# SCH.net
KiCad netlist of a schematic drawn in EasyEDA Pro
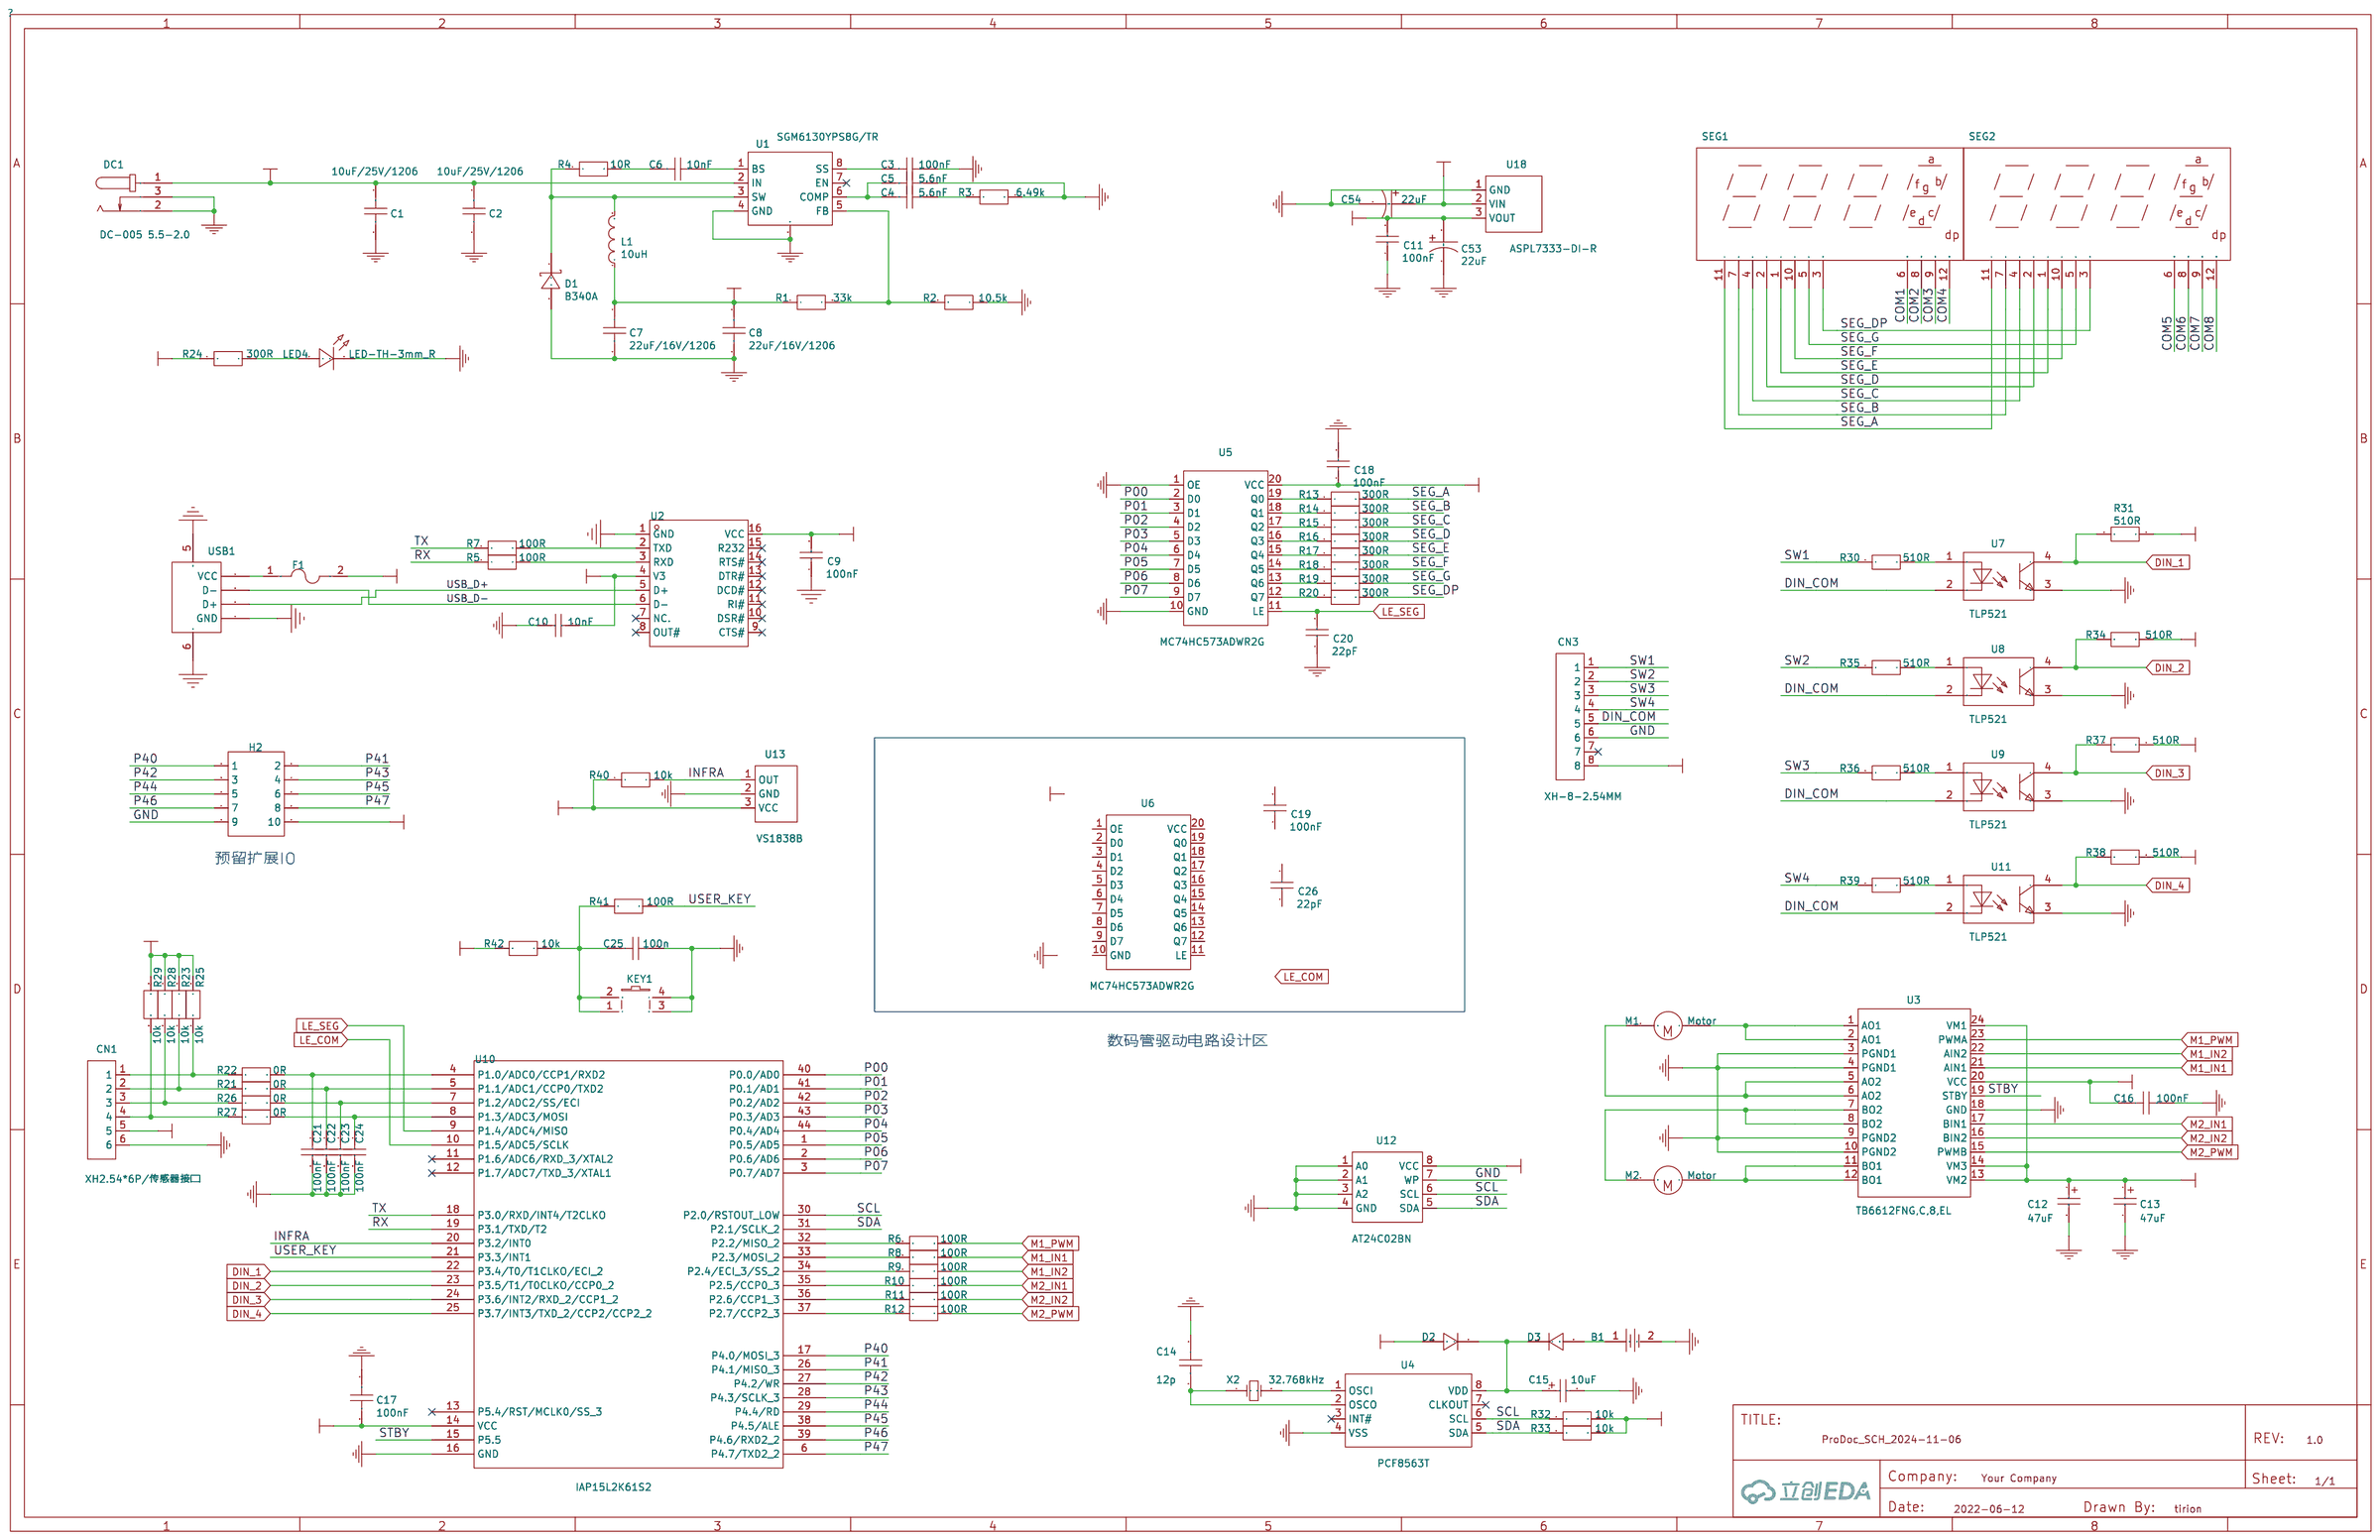
[diagram p0: schematic sheet]

(export (version "E")
  (design (tool "Eeschema 10.0.6"))
  (components
    (comp (ref "B1")
      (value "CR1220-2")
      (footprint "easyedapro:BAT-SMD_CR1220-2")
      (fields (field (name "Manufacturer") "Q&J"))
      (libsource (lib "easyedapro") (part "CR1220-2"))
    )
    (comp (ref "C1")
      (value "10uF/25V/1206")
      (footprint "easyedapro:C1206")
      (libsource (lib "easyedapro") (part "10uF/25V/1206"))
    )
    (comp (ref "C2")
      (value "10uF/25V/1206")
      (footprint "easyedapro:C1206")
      (libsource (lib "easyedapro") (part "10uF/25V/1206"))
    )
    (comp (ref "C3") (value "100nF") (footprint "easyedapro:C0805") (libsource (lib "") (part "100nF_1")))
    (comp (ref "C4")
      (value "5.6nF")
      (footprint "easyedapro:C0805")
      (libsource (lib "easyedapro") (part "5.6nF"))
    )
    (comp (ref "C5")
      (value "5.6nF")
      (footprint "easyedapro:C0805")
      (libsource (lib "easyedapro") (part "5.6nF"))
    )
    (comp (ref "C6")
      (value "10nF")
      (footprint "easyedapro:C0805")
      (libsource (lib "easyedapro") (part "10nF"))
    )
    (comp (ref "C7")
      (value "22uF/16V/1206")
      (footprint "easyedapro:C1206")
      (libsource (lib "easyedapro") (part "22uF/16V/1206"))
    )
    (comp (ref "C8")
      (value "22uF/16V/1206")
      (footprint "easyedapro:C1206")
      (libsource (lib "easyedapro") (part "22uF/16V/1206"))
    )
    (comp (ref "C9")
      (value "100nF")
      (footprint "easyedapro:C_C0805")
      (fields (field (name "Manufacturer Part") "0805F104M500NT") (field (name "Manufacturer") "FH"))
      (libsource (lib "easyedapro") (part "100nF"))
    )
    (comp (ref "C10")
      (value "10nF")
      (footprint "easyedapro:C_C0805")
      (fields (field (name "Manufacturer Part") "0805F104M500NT") (field (name "Manufacturer") "FH"))
      (libsource (lib "easyedapro") (part "100nF"))
    )
    (comp (ref "C11")
      (value "100nF")
      (footprint "easyedapro:C_C0805")
      (fields (field (name "Manufacturer Part") "0805F104M500NT") (field (name "Manufacturer") "FH"))
      (libsource (lib "easyedapro") (part "100nF"))
    )
    (comp (ref "C12")
      (value "47uF")
      (footprint "easyedapro:C_Ele_SMD_3x5.4mm")
      (libsource (lib "easyedapro") (part "CAP"))
    )
    (comp (ref "C13")
      (value "47uF")
      (footprint "easyedapro:C_Ele_SMD_3x5.4mm")
      (libsource (lib "easyedapro") (part "CAP"))
    )
    (comp (ref "C14")
      (value "12p")
      (footprint "easyedapro:C0805")
      (libsource (lib "easyedapro") (part "12p"))
    )
    (comp (ref "C15")
      (value "10uF")
      (footprint "easyedapro:C_Ele_SMD_3x5.4mm")
      (libsource (lib "easyedapro") (part "CAP"))
    )
    (comp (ref "C16") (value "100nF") (footprint "easyedapro:C0805") (libsource (lib "") (part "100nF_1")))
    (comp (ref "C17") (value "100nF") (footprint "easyedapro:C0805") (libsource (lib "") (part "100nF_1")))
    (comp (ref "C18")
      (value "100nF")
      (footprint "easyedapro:C_C0805")
      (fields (field (name "Manufacturer Part") "0805F104M500NT") (field (name "Manufacturer") "FH"))
      (libsource (lib "easyedapro") (part "100nF"))
    )
    (comp (ref "C19")
      (value "100nF")
      (footprint "easyedapro:C_C0805")
      (fields (field (name "Manufacturer Part") "0805F104M500NT") (field (name "Manufacturer") "FH"))
      (libsource (lib "easyedapro") (part "100nF"))
    )
    (comp (ref "C20")
      (value "22pF")
      (footprint "easyedapro:C_C0805")
      (fields (field (name "Manufacturer Part") "0805F104M500NT") (field (name "Manufacturer") "FH"))
      (libsource (lib "easyedapro") (part "100nF"))
    )
    (comp (ref "C21")
      (value "100nF")
      (footprint "easyedapro:C_C0805")
      (fields (field (name "Manufacturer Part") "0805F104M500NT") (field (name "Manufacturer") "FH"))
      (libsource (lib "easyedapro") (part "100nF"))
    )
    (comp (ref "C22")
      (value "100nF")
      (footprint "easyedapro:C_C0805")
      (fields (field (name "Manufacturer Part") "0805F104M500NT") (field (name "Manufacturer") "FH"))
      (libsource (lib "easyedapro") (part "100nF"))
    )
    (comp (ref "C23")
      (value "100nF")
      (footprint "easyedapro:C_C0805")
      (fields (field (name "Manufacturer Part") "0805F104M500NT") (field (name "Manufacturer") "FH"))
      (libsource (lib "easyedapro") (part "100nF"))
    )
    (comp (ref "C24")
      (value "100nF")
      (footprint "easyedapro:C_C0805")
      (fields (field (name "Manufacturer Part") "0805F104M500NT") (field (name "Manufacturer") "FH"))
      (libsource (lib "easyedapro") (part "100nF"))
    )
    (comp (ref "C25")
      (value "100n")
      (footprint "easyedapro:C0805")
      (libsource (lib "easyedapro") (part "100n"))
    )
    (comp (ref "C26")
      (value "22pF")
      (footprint "easyedapro:C_C0805")
      (fields (field (name "Manufacturer Part") "0805F104M500NT") (field (name "Manufacturer") "FH"))
      (libsource (lib "easyedapro") (part "100nF"))
    )
    (comp (ref "C53")
      (value "22uF")
      (footprint "easyedapro:CAP-SMD_BD6.3-L6.6-W6.6-FD")
      (fields (field (name "Manufacturer") "Honor Elec"))
      (libsource (lib "easyedapro") (part "22uF"))
    )
    (comp (ref "C54")
      (value "22uF")
      (footprint "easyedapro:CAP-SMD_BD6.3-L6.6-W6.6-FD")
      (fields (field (name "Manufacturer") "Honor Elec"))
      (libsource (lib "easyedapro") (part "22uF"))
    )
    (comp (ref "CN1")
      (value "XH2.54*6P/传感器接口")
      (footprint "easyedapro:CONN-TH_XH2.54-6P")
      (fields (field (name "Manufacturer Part") "XH2.54*6P_直插"))
      (libsource (lib "easyedapro") (part "XH2.54*6P/传感器接口"))
    )
    (comp (ref "CN3")
      (value "XH-8-2.54MM")
      (footprint "easyedapro:CONN-TH_8P-P2.50-XH2.54-8P")
      (libsource (lib "easyedapro") (part "XH-8-2.54MM"))
    )
    (comp (ref "D1")
      (value "B340A")
      (footprint "easyedapro:SMA_L4.3-W2.6-LS5.2-RD")
      (fields (field (name "Manufacturer") "MDD"))
      (libsource (lib "easyedapro") (part "B340A"))
    )
    (comp (ref "D2")
      (value "1N4148")
      (footprint "easyedapro:DO-35_BD2.0-L4.2-P8.20-D0.5-RD")
      (fields (field (name "Manufacturer") "STMicroelectronics"))
      (libsource (lib "easyedapro") (part "1N4148"))
    )
    (comp (ref "D3")
      (value "1N4148")
      (footprint "easyedapro:DO-35_BD2.0-L4.2-P8.20-D0.5-RD")
      (fields (field (name "Manufacturer") "STMicroelectronics"))
      (libsource (lib "easyedapro") (part "1N4148"))
    )
    (comp (ref "DC1")
      (value "DC-005 5.5-2.0")
      (footprint "easyedapro:DC-IN-TH_DC005")
      (fields (field (name "Manufacturer") "Shenzhen Cankemeng"))
      (libsource (lib "easyedapro") (part "DC-005 5.5-2.0"))
    )
    (comp (ref "F1")
      (value "ASMD1210-075")
      (footprint "easyedapro:F1210")
      (description "最大电压:6V;最大电流:100A;保持电流:750mA;跳闸电流:1.5A;")
      (fields (field (name "Manufacturer") "JDTfuse(集电通)"))
      (libsource (lib "easyedapro") (part "ASMD1210-075"))
    )
    (comp (ref "H2")
      (value "HDR-F-2.54_2x5")
      (footprint "easyedapro:HDR-F-2.54_2X5")
      (libsource (lib "easyedapro") (part "HDR-F-2.54_2x5"))
    )
    (comp (ref "KEY1")
      (value "K4-6×6_SMD")
      (footprint "easyedapro:KEY-SMD_4P-L6.0-W6.0-P3.90-LS10.0")
      (fields (field (name "Manufacturer Part") "K2-6639SP-D4SC-04") (field (name "Manufacturer") "韩国韩荣"))
      (libsource (lib "easyedapro") (part "K4-6×6_SMD"))
    )
    (comp (ref "L1")
      (value "10uH")
      (footprint "easyedapro:IND-SMD_L8.3-W8.3")
      (fields
        (field (name "Manufacturer Part") "1217AS-H-100M=P3")
        (field (name "Manufacturer") "Murata Electronics")
      )
      (libsource (lib "easyedapro") (part "10uH"))
    )
    (comp (ref "LED4")
      (value "LED-TH-3mm_R")
      (footprint "easyedapro:LED-TH_BD3.0_RED")
      (fields
        (field (name "Manufacturer Part") "204-10SDRD/S530-A3-L")
        (field (name "Manufacturer") "EVERLIGHT(台湾亿光)")
      )
      (libsource (lib "easyedapro") (part "LED-TH-3mm_R"))
    )
    (comp (ref "M1")
      (value "Motor")
      (footprint "easyedapro:CONN-TH_2P-P5.08-WJ500V-5.08-2P")
      (libsource (lib "easyedapro") (part "Motor"))
    )
    (comp (ref "M2")
      (value "Motor")
      (footprint "easyedapro:CONN-TH_2P-P5.08-WJ500V-5.08-2P")
      (libsource (lib "easyedapro") (part "Motor"))
    )
    (comp (ref "R1") (value "33k") (footprint "easyedapro:R0805") (libsource (lib "easyedapro") (part "33k")))
    (comp (ref "R2")
      (value "10.5k")
      (footprint "easyedapro:R0805")
      (libsource (lib "easyedapro") (part "10.5k"))
    )
    (comp (ref "R3")
      (value "6.49k")
      (footprint "easyedapro:R0805")
      (libsource (lib "easyedapro") (part "6.49k"))
    )
    (comp (ref "R4") (value "10R") (footprint "easyedapro:R0805") (libsource (lib "easyedapro") (part "10R")))
    (comp (ref "R5")
      (value "100R")
      (footprint "easyedapro:R0805")
      (libsource (lib "easyedapro") (part "100R"))
    )
    (comp (ref "R6")
      (value "100R")
      (footprint "easyedapro:R0805")
      (libsource (lib "easyedapro") (part "100R"))
    )
    (comp (ref "R7")
      (value "100R")
      (footprint "easyedapro:R0805")
      (libsource (lib "easyedapro") (part "100R"))
    )
    (comp (ref "R8")
      (value "100R")
      (footprint "easyedapro:R0805")
      (libsource (lib "easyedapro") (part "100R"))
    )
    (comp (ref "R9")
      (value "100R")
      (footprint "easyedapro:R0805")
      (libsource (lib "easyedapro") (part "100R"))
    )
    (comp (ref "R10")
      (value "100R")
      (footprint "easyedapro:R0805")
      (libsource (lib "easyedapro") (part "100R"))
    )
    (comp (ref "R11")
      (value "100R")
      (footprint "easyedapro:R0805")
      (libsource (lib "easyedapro") (part "100R"))
    )
    (comp (ref "R12")
      (value "100R")
      (footprint "easyedapro:R0805")
      (libsource (lib "easyedapro") (part "100R"))
    )
    (comp (ref "R13")
      (value "300R")
      (footprint "easyedapro:R0805")
      (libsource (lib "easyedapro") (part "300R"))
    )
    (comp (ref "R14")
      (value "300R")
      (footprint "easyedapro:R0805")
      (libsource (lib "easyedapro") (part "300R"))
    )
    (comp (ref "R15")
      (value "300R")
      (footprint "easyedapro:R0805")
      (libsource (lib "easyedapro") (part "300R"))
    )
    (comp (ref "R16")
      (value "300R")
      (footprint "easyedapro:R0805")
      (libsource (lib "easyedapro") (part "300R"))
    )
    (comp (ref "R17")
      (value "300R")
      (footprint "easyedapro:R0805")
      (libsource (lib "easyedapro") (part "300R"))
    )
    (comp (ref "R18")
      (value "300R")
      (footprint "easyedapro:R0805")
      (libsource (lib "easyedapro") (part "300R"))
    )
    (comp (ref "R19")
      (value "300R")
      (footprint "easyedapro:R0805")
      (libsource (lib "easyedapro") (part "300R"))
    )
    (comp (ref "R20")
      (value "300R")
      (footprint "easyedapro:R0805")
      (libsource (lib "easyedapro") (part "300R"))
    )
    (comp (ref "R21") (value "0R") (footprint "easyedapro:R0805") (libsource (lib "easyedapro") (part "0R")))
    (comp (ref "R22") (value "0R") (footprint "easyedapro:R0805") (libsource (lib "easyedapro") (part "0R")))
    (comp (ref "R23")
      (value "10k")
      (footprint "easyedapro:R0805")
      (libsource (lib "easyedapro") (part "10k"))
    )
    (comp (ref "R24")
      (value "300R")
      (footprint "easyedapro:R0805")
      (libsource (lib "easyedapro") (part "300R"))
    )
    (comp (ref "R25")
      (value "10k")
      (footprint "easyedapro:R0805")
      (libsource (lib "easyedapro") (part "10k"))
    )
    (comp (ref "R26") (value "0R") (footprint "easyedapro:R0805") (libsource (lib "easyedapro") (part "0R")))
    (comp (ref "R27") (value "0R") (footprint "easyedapro:R0805") (libsource (lib "easyedapro") (part "0R")))
    (comp (ref "R28")
      (value "10k")
      (footprint "easyedapro:R0805")
      (libsource (lib "easyedapro") (part "10k"))
    )
    (comp (ref "R29")
      (value "10k")
      (footprint "easyedapro:R0805")
      (libsource (lib "easyedapro") (part "10k"))
    )
    (comp (ref "R30")
      (value "510R")
      (footprint "easyedapro:R0805")
      (libsource (lib "easyedapro") (part "510R"))
    )
    (comp (ref "R31")
      (value "510R")
      (footprint "easyedapro:R0805")
      (libsource (lib "easyedapro") (part "510R"))
    )
    (comp (ref "R32")
      (value "10k")
      (footprint "easyedapro:R0805")
      (libsource (lib "easyedapro") (part "10k"))
    )
    (comp (ref "R33")
      (value "10k")
      (footprint "easyedapro:R0805")
      (libsource (lib "easyedapro") (part "10k"))
    )
    (comp (ref "R34")
      (value "510R")
      (footprint "easyedapro:R0805")
      (libsource (lib "easyedapro") (part "510R"))
    )
    (comp (ref "R35")
      (value "510R")
      (footprint "easyedapro:R0805")
      (libsource (lib "easyedapro") (part "510R"))
    )
    (comp (ref "R36")
      (value "510R")
      (footprint "easyedapro:R0805")
      (libsource (lib "easyedapro") (part "510R"))
    )
    (comp (ref "R37")
      (value "510R")
      (footprint "easyedapro:R0805")
      (libsource (lib "easyedapro") (part "510R"))
    )
    (comp (ref "R38")
      (value "510R")
      (footprint "easyedapro:R0805")
      (libsource (lib "easyedapro") (part "510R"))
    )
    (comp (ref "R39")
      (value "510R")
      (footprint "easyedapro:R0805")
      (libsource (lib "easyedapro") (part "510R"))
    )
    (comp (ref "R40")
      (value "10k")
      (footprint "easyedapro:R0805")
      (libsource (lib "easyedapro") (part "10k"))
    )
    (comp (ref "R41")
      (value "100R")
      (footprint "easyedapro:R0805")
      (libsource (lib "easyedapro") (part "100R"))
    )
    (comp (ref "R42")
      (value "10k")
      (footprint "easyedapro:R0805")
      (libsource (lib "easyedapro") (part "10k"))
    )
    (comp (ref "SEG1")
      (value "0.36寸4位数码管")
      (footprint "easyedapro:LED-SEG-TH_FJ5461AH")
      (fields (field (name "Manufacturer Part") "FJ5461BH 纯红") (field (name "Manufacturer") "ReliaPro"))
      (libsource (lib "easyedapro") (part "0.36寸4位数码管"))
    )
    (comp (ref "SEG2")
      (value "0.36寸4位数码管")
      (footprint "easyedapro:LED-SEG-TH_FJ5461AH")
      (fields (field (name "Manufacturer Part") "FJ5461BH 纯红") (field (name "Manufacturer") "ReliaPro"))
      (libsource (lib "easyedapro") (part "0.36寸4位数码管"))
    )
    (comp (ref "U1")
      (value "SGM6130YPS8G/TR")
      (footprint "easyedapro:SOIC-8_L5.0-W4.0-P1.27-LS6.0-BL-EP2.0")
      (fields (field (name "Manufacturer") "SGMICRO"))
      (libsource (lib "easyedapro") (part "SGM6130YPS8G/TR"))
    )
    (comp (ref "U2")
      (value "CH340C")
      (footprint "easyedapro:SOP-16_L10.0-W3.9-P1.27-LS6.0-BL")
      (description "应用功能:收发器;接口协议:USB 2.0;数据速率:2Mbps;")
      (fields (field (name "Manufacturer") "WCH(南京沁恒)"))
      (libsource (lib "easyedapro") (part "CH340C"))
    )
    (comp (ref "U3")
      (value "TB6612FNG,C,8,EL")
      (footprint "easyedapro:SSOP-24_L8.3-W5.6-P0.65-LS7.6-BL")
      (fields (field (name "Manufacturer") "TOSHIBA"))
      (libsource (lib "easyedapro") (part "TB6612FNG,C,8,EL"))
    )
    (comp (ref "U4")
      (value "PCF8563T")
      (footprint "easyedapro:SOIC-8_L5.0-W4.0-P1.27-LS6.0-BL")
      (fields (field (name "Manufacturer Part") "PCF8563T/5,518") (field (name "Manufacturer") "NXP"))
      (libsource (lib "easyedapro") (part "PCF8563T"))
    )
    (comp (ref "U5")
      (value "MC74HC573ADWR2G")
      (footprint "easyedapro:SOIC-20_L13.0-W7.6-P1.27-LS10.3-BL")
      (fields (field (name "Manufacturer") "ON Semicon"))
      (libsource (lib "easyedapro") (part "MC74HC573ADWR2G"))
    )
    (comp (ref "U6")
      (value "MC74HC573ADWR2G")
      (footprint "easyedapro:SOIC-20_L13.0-W7.6-P1.27-LS10.3-BL")
      (fields (field (name "Manufacturer") "ON Semicon"))
      (libsource (lib "easyedapro") (part "MC74HC573ADWR2G"))
    )
    (comp (ref "U7")
      (value "TLP521")
      (footprint "easyedapro:SOP-4_L6.4-W4.6-P2.54-LS10.2-TL")
      (libsource (lib "easyedapro") (part "TLP521"))
    )
    (comp (ref "U8")
      (value "TLP521")
      (footprint "easyedapro:SOP-4_L6.4-W4.6-P2.54-LS10.2-TL")
      (libsource (lib "easyedapro") (part "TLP521"))
    )
    (comp (ref "U9")
      (value "TLP521")
      (footprint "easyedapro:SOP-4_L6.4-W4.6-P2.54-LS10.2-TL")
      (libsource (lib "easyedapro") (part "TLP521"))
    )
    (comp (ref "U10")
      (value "IAP15L2K61S2")
      (footprint "easyedapro:QFP-LQFP-44")
      (libsource (lib "easyedapro") (part "IAP15L2K61S2"))
    )
    (comp (ref "U11")
      (value "TLP521")
      (footprint "easyedapro:SOP-4_L6.4-W4.6-P2.54-LS10.2-TL")
      (libsource (lib "easyedapro") (part "TLP521"))
    )
    (comp (ref "U12")
      (value "AT24C02BN")
      (footprint "easyedapro:SOP-8_L4.9-W3.9-P1.27-LS6.0-TL")
      (libsource (lib "easyedapro") (part "AT24C02BN"))
    )
    (comp (ref "U13")
      (value "VS1838B")
      (footprint "easyedapro:OPTO-TH_VS1838B")
      (libsource (lib "easyedapro") (part "VS1838B"))
    )
    (comp (ref "U18")
      (value "ASPL7333-DI-R")
      (footprint "easyedapro:SOT-89-3_L4.5-W2.5-P1.50-LS4.2-BR")
      (fields (field (name "Manufacturer") "Ascend(安森德)"))
      (libsource (lib "easyedapro") (part "ASPL7333-DI-R"))
    )
    (comp (ref "USB1")
      (value "921-111A1010D10200")
      (footprint "easyedapro:USB-B_TH_USB-B-FEMALE-90")
      (description "连接器类型:Type-B;标准:USB 2.0;公母:母;端口数量:1;触点数量:4P;")
      (fields (field (name "Manufacturer") "精拓金"))
      (libsource (lib "easyedapro") (part "USB-B-Female-90"))
    )
    (comp (ref "X2")
      (value "32.768kHz")
      (footprint "easyedapro:OSC-TH_BD2.0-P0.70-D0.3")
      (description "晶振类型:直插晶振;频率:32.768kHz;常温频差:±10ppm;外接负载电容:12.5pF;频率稳定度(全温):-;")
      (fields (field (name "Manufacturer Part") "X206032768KGB2SC") (field (name "Manufacturer") "YXC(扬兴晶振)"))
      (libsource (lib "easyedapro") (part "X206032768KGB2SC"))
    )
  )
  (nets
    (net (code "1") (name "+3V3") (class "Default")
      (node (ref "C10") (pin "1") (pinfunction "1_1") (pintype "unspecified"))
      (node (ref "C11") (pin "2") (pinfunction "2_2") (pintype "unspecified"))
      (node (ref "C16") (pin "1") (pinfunction "1_1") (pintype "unspecified"))
      (node (ref "C17") (pin "2") (pinfunction "2_2") (pintype "unspecified"))
      (node (ref "C18") (pin "1") (pinfunction "1_1") (pintype "unspecified"))
      (node (ref "C53") (pin "1") (pinfunction "1_1") (pintype "unspecified"))
      (node (ref "C7") (pin "1") (pinfunction "1_1") (pintype "unspecified"))
      (node (ref "C8") (pin "1") (pinfunction "1_1") (pintype "unspecified"))
      (node (ref "C9") (pin "2") (pinfunction "2_2") (pintype "unspecified"))
      (node (ref "CN1") (pin "5") (pinfunction "5_5") (pintype "unspecified"))
      (node (ref "D2") (pin "2") (pinfunction "2_2") (pintype "unspecified"))
      (node (ref "H2") (pin "10") (pinfunction "10_10") (pintype "unspecified"))
      (node (ref "L1") (pin "1") (pinfunction "1_1") (pintype "unspecified"))
      (node (ref "R1") (pin "1") (pinfunction "1_1") (pintype "unspecified"))
      (node (ref "R23") (pin "1") (pinfunction "1_1") (pintype "unspecified"))
      (node (ref "R24") (pin "2") (pinfunction "2_2") (pintype "unspecified"))
      (node (ref "R25") (pin "1") (pinfunction "1_1") (pintype "unspecified"))
      (node (ref "R28") (pin "1") (pinfunction "1_1") (pintype "unspecified"))
      (node (ref "R29") (pin "1") (pinfunction "1_1") (pintype "unspecified"))
      (node (ref "R31") (pin "1") (pinfunction "1_1") (pintype "unspecified"))
      (node (ref "R32") (pin "2") (pinfunction "2_2") (pintype "unspecified"))
      (node (ref "R33") (pin "2") (pinfunction "2_2") (pintype "unspecified"))
      (node (ref "R34") (pin "1") (pinfunction "1_1") (pintype "unspecified"))
      (node (ref "R37") (pin "1") (pinfunction "1_1") (pintype "unspecified"))
      (node (ref "R38") (pin "1") (pinfunction "1_1") (pintype "unspecified"))
      (node (ref "R40") (pin "1") (pinfunction "1_1") (pintype "unspecified"))
      (node (ref "R42") (pin "2") (pinfunction "2_2") (pintype "unspecified"))
      (node (ref "U10") (pin "14") (pinfunction "VCC_14") (pintype "unspecified"))
      (node (ref "U12") (pin "8") (pinfunction "VCC_8") (pintype "unspecified"))
      (node (ref "U13") (pin "3") (pinfunction "VCC_3") (pintype "unspecified"))
      (node (ref "U18") (pin "3") (pinfunction "VOUT_3") (pintype "unspecified"))
      (node (ref "U2") (pin "16") (pinfunction "VCC_16") (pintype "unspecified"))
      (node (ref "U2") (pin "4") (pinfunction "V3_4") (pintype "unspecified"))
      (node (ref "U3") (pin "20") (pinfunction "VCC_20") (pintype "unspecified"))
      (node (ref "U5") (pin "20") (pinfunction "VCC_20") (pintype "unspecified"))
    )
    (net (code "2") (name "/COM1") (class "Default")
      (node (ref "SEG1") (pin "6") (pinfunction "DIG4_6") (pintype "input"))
    )
    (net (code "3") (name "/COM2") (class "Default")
      (node (ref "SEG1") (pin "8") (pinfunction "DIG3_8") (pintype "input"))
    )
    (net (code "4") (name "/COM3") (class "Default")
      (node (ref "SEG1") (pin "9") (pinfunction "DIG2_9") (pintype "input"))
    )
    (net (code "5") (name "/COM4") (class "Default")
      (node (ref "SEG1") (pin "12") (pinfunction "DIG1_12") (pintype "input"))
    )
    (net (code "6") (name "/COM5") (class "Default")
      (node (ref "SEG2") (pin "6") (pinfunction "DIG4_6") (pintype "input"))
    )
    (net (code "7") (name "/COM6") (class "Default")
      (node (ref "SEG2") (pin "8") (pinfunction "DIG3_8") (pintype "input"))
    )
    (net (code "8") (name "/COM7") (class "Default")
      (node (ref "SEG2") (pin "9") (pinfunction "DIG2_9") (pintype "input"))
    )
    (net (code "9") (name "/COM8") (class "Default")
      (node (ref "SEG2") (pin "12") (pinfunction "DIG1_12") (pintype "input"))
    )
    (net (code "10") (name "/DIN_COM") (class "Default")
      (node (ref "CN3") (pin "5") (pinfunction "5_5") (pintype "unspecified"))
      (node (ref "U11") (pin "2") (pinfunction "2_2") (pintype "unspecified"))
      (node (ref "U7") (pin "2") (pinfunction "2_2") (pintype "unspecified"))
      (node (ref "U8") (pin "2") (pinfunction "2_2") (pintype "unspecified"))
      (node (ref "U9") (pin "2") (pinfunction "2_2") (pintype "unspecified"))
    )
    (net (code "11") (name "/INFRA") (class "Default")
      (node (ref "R40") (pin "2") (pinfunction "2_2") (pintype "unspecified"))
      (node (ref "U10") (pin "20") (pinfunction "P3.2/INT0_20") (pintype "unspecified"))
      (node (ref "U13") (pin "1") (pinfunction "OUT_1") (pintype "unspecified"))
    )
    (net (code "12") (name "/P00") (class "Default")
      (node (ref "U10") (pin "40") (pinfunction "P0.0/AD0_40") (pintype "bidirectional"))
      (node (ref "U5") (pin "2") (pinfunction "D0_2") (pintype "unspecified"))
    )
    (net (code "13") (name "/P01") (class "Default")
      (node (ref "U10") (pin "41") (pinfunction "P0.1/AD1_41") (pintype "bidirectional"))
      (node (ref "U5") (pin "3") (pinfunction "D1_3") (pintype "unspecified"))
    )
    (net (code "14") (name "/P02") (class "Default")
      (node (ref "U10") (pin "42") (pinfunction "P0.2/AD2_42") (pintype "bidirectional"))
      (node (ref "U5") (pin "4") (pinfunction "D2_4") (pintype "unspecified"))
    )
    (net (code "15") (name "/P03") (class "Default")
      (node (ref "U10") (pin "43") (pinfunction "P0.3/AD3_43") (pintype "bidirectional"))
      (node (ref "U5") (pin "5") (pinfunction "D3_5") (pintype "unspecified"))
    )
    (net (code "16") (name "/P04") (class "Default")
      (node (ref "U10") (pin "44") (pinfunction "P0.4/AD4_44") (pintype "bidirectional"))
      (node (ref "U5") (pin "6") (pinfunction "D4_6") (pintype "unspecified"))
    )
    (net (code "17") (name "/P05") (class "Default")
      (node (ref "U10") (pin "1") (pinfunction "P0.5/AD5_1") (pintype "bidirectional"))
      (node (ref "U5") (pin "7") (pinfunction "D5_7") (pintype "unspecified"))
    )
    (net (code "18") (name "/P06") (class "Default")
      (node (ref "U10") (pin "2") (pinfunction "P0.6/AD6_2") (pintype "bidirectional"))
      (node (ref "U5") (pin "8") (pinfunction "D6_8") (pintype "unspecified"))
    )
    (net (code "19") (name "/P07") (class "Default")
      (node (ref "U10") (pin "3") (pinfunction "P0.7/AD7_3") (pintype "bidirectional"))
      (node (ref "U5") (pin "9") (pinfunction "D7_9") (pintype "unspecified"))
    )
    (net (code "20") (name "/P40") (class "Default")
      (node (ref "H2") (pin "1") (pinfunction "1_1") (pintype "unspecified"))
      (node (ref "U10") (pin "17") (pinfunction "P4.0/MOSI_3_17") (pintype "bidirectional"))
    )
    (net (code "21") (name "/P41") (class "Default")
      (node (ref "H2") (pin "2") (pinfunction "2_2") (pintype "unspecified"))
      (node (ref "U10") (pin "26") (pinfunction "P4.1/MISO_3_26") (pintype "bidirectional"))
    )
    (net (code "22") (name "/P42") (class "Default")
      (node (ref "H2") (pin "3") (pinfunction "3_3") (pintype "unspecified"))
      (node (ref "U10") (pin "27") (pinfunction "P4.2/WR_27") (pintype "unspecified"))
    )
    (net (code "23") (name "/P43") (class "Default")
      (node (ref "H2") (pin "4") (pinfunction "4_4") (pintype "unspecified"))
      (node (ref "U10") (pin "28") (pinfunction "P4.3/SCLK_3_28") (pintype "bidirectional"))
    )
    (net (code "24") (name "/P44") (class "Default")
      (node (ref "H2") (pin "5") (pinfunction "5_5") (pintype "unspecified"))
      (node (ref "U10") (pin "29") (pinfunction "P4.4/RD_29") (pintype "unspecified"))
    )
    (net (code "25") (name "/P45") (class "Default")
      (node (ref "H2") (pin "6") (pinfunction "6_6") (pintype "unspecified"))
      (node (ref "U10") (pin "38") (pinfunction "P4.5/ALE_38") (pintype "unspecified"))
    )
    (net (code "26") (name "/P46") (class "Default")
      (node (ref "H2") (pin "7") (pinfunction "7_7") (pintype "unspecified"))
      (node (ref "U10") (pin "39") (pinfunction "P4.6/RXD2_2_39") (pintype "unspecified"))
    )
    (net (code "27") (name "/P47") (class "Default")
      (node (ref "H2") (pin "8") (pinfunction "8_8") (pintype "unspecified"))
      (node (ref "U10") (pin "6") (pinfunction "P4.7/TXD2_2_6") (pintype "bidirectional"))
    )
    (net (code "28") (name "/RX") (class "Default")
      (node (ref "R5") (pin "1") (pinfunction "1_1") (pintype "unspecified"))
      (node (ref "U10") (pin "19") (pinfunction "P3.1/TXD/T2_19") (pintype "unspecified"))
    )
    (net (code "29") (name "/SCL") (class "Default")
      (node (ref "R32") (pin "1") (pinfunction "1_1") (pintype "unspecified"))
      (node (ref "U10") (pin "30") (pinfunction "P2.0/RSTOUT_LOW_30") (pintype "bidirectional"))
      (node (ref "U12") (pin "6") (pinfunction "SCL_6") (pintype "unspecified"))
      (node (ref "U4") (pin "6") (pinfunction "SCL_6") (pintype "unspecified"))
    )
    (net (code "30") (name "/SDA") (class "Default")
      (node (ref "R33") (pin "1") (pinfunction "1_1") (pintype "unspecified"))
      (node (ref "U10") (pin "31") (pinfunction "P2.1/SCLK_2_31") (pintype "bidirectional"))
      (node (ref "U12") (pin "5") (pinfunction "SDA_5") (pintype "unspecified"))
      (node (ref "U4") (pin "5") (pinfunction "SDA_5") (pintype "unspecified"))
    )
    (net (code "31") (name "/SEG_A") (class "Default")
      (node (ref "R13") (pin "2") (pinfunction "2_2") (pintype "unspecified"))
      (node (ref "SEG1") (pin "11") (pinfunction "A_11") (pintype "input"))
      (node (ref "SEG2") (pin "11") (pinfunction "A_11") (pintype "input"))
    )
    (net (code "32") (name "/SEG_B") (class "Default")
      (node (ref "R14") (pin "2") (pinfunction "2_2") (pintype "unspecified"))
      (node (ref "SEG1") (pin "7") (pinfunction "B_7") (pintype "input"))
      (node (ref "SEG2") (pin "7") (pinfunction "B_7") (pintype "input"))
    )
    (net (code "33") (name "/SEG_C") (class "Default")
      (node (ref "R15") (pin "2") (pinfunction "2_2") (pintype "unspecified"))
      (node (ref "SEG1") (pin "4") (pinfunction "C_4") (pintype "input"))
      (node (ref "SEG2") (pin "4") (pinfunction "C_4") (pintype "input"))
    )
    (net (code "34") (name "/SEG_D") (class "Default")
      (node (ref "R16") (pin "2") (pinfunction "2_2") (pintype "unspecified"))
      (node (ref "SEG1") (pin "2") (pinfunction "D_2") (pintype "input"))
      (node (ref "SEG2") (pin "2") (pinfunction "D_2") (pintype "input"))
    )
    (net (code "35") (name "/SEG_DP") (class "Default")
      (node (ref "R20") (pin "2") (pinfunction "2_2") (pintype "unspecified"))
      (node (ref "SEG1") (pin "3") (pinfunction "DP_3") (pintype "input"))
      (node (ref "SEG2") (pin "3") (pinfunction "DP_3") (pintype "input"))
    )
    (net (code "36") (name "/SEG_E") (class "Default")
      (node (ref "R17") (pin "2") (pinfunction "2_2") (pintype "unspecified"))
      (node (ref "SEG1") (pin "1") (pinfunction "E_1") (pintype "input"))
      (node (ref "SEG2") (pin "1") (pinfunction "E_1") (pintype "input"))
    )
    (net (code "37") (name "/SEG_F") (class "Default")
      (node (ref "R18") (pin "2") (pinfunction "2_2") (pintype "unspecified"))
      (node (ref "SEG1") (pin "10") (pinfunction "F_10") (pintype "input"))
      (node (ref "SEG2") (pin "10") (pinfunction "F_10") (pintype "input"))
    )
    (net (code "38") (name "/SEG_G") (class "Default")
      (node (ref "R19") (pin "2") (pinfunction "2_2") (pintype "unspecified"))
      (node (ref "SEG1") (pin "5") (pinfunction "G_5") (pintype "input"))
      (node (ref "SEG2") (pin "5") (pinfunction "G_5") (pintype "input"))
    )
    (net (code "39") (name "/STBY") (class "Default")
      (node (ref "U10") (pin "15") (pinfunction "P5.5_15") (pintype "unspecified"))
      (node (ref "U3") (pin "19") (pinfunction "STBY_19") (pintype "unspecified"))
    )
    (net (code "40") (name "/SW1") (class "Default")
      (node (ref "CN3") (pin "1") (pinfunction "1_1") (pintype "unspecified"))
      (node (ref "R30") (pin "1") (pinfunction "1_1") (pintype "unspecified"))
    )
    (net (code "41") (name "/SW2") (class "Default")
      (node (ref "CN3") (pin "2") (pinfunction "2_2") (pintype "unspecified"))
      (node (ref "R35") (pin "1") (pinfunction "1_1") (pintype "unspecified"))
    )
    (net (code "42") (name "/SW3") (class "Default")
      (node (ref "CN3") (pin "3") (pinfunction "3_3") (pintype "unspecified"))
      (node (ref "R36") (pin "1") (pinfunction "1_1") (pintype "unspecified"))
    )
    (net (code "43") (name "/SW4") (class "Default")
      (node (ref "CN3") (pin "4") (pinfunction "4_4") (pintype "unspecified"))
      (node (ref "R39") (pin "1") (pinfunction "1_1") (pintype "unspecified"))
    )
    (net (code "44") (name "/TX") (class "Default")
      (node (ref "R7") (pin "1") (pinfunction "1_1") (pintype "unspecified"))
      (node (ref "U10") (pin "18") (pinfunction "P3.0/RXD/INT4/T2CLKO_18") (pintype "unspecified"))
    )
    (net (code "45") (name "/USB_D+") (class "Default")
      (node (ref "U2") (pin "5") (pinfunction "D+_5") (pintype "unspecified"))
      (node (ref "USB1") (pin "3") (pinfunction "D+_3") (pintype "input"))
    )
    (net (code "46") (name "/USB_D-") (class "Default")
      (node (ref "U2") (pin "6") (pinfunction "D-_6") (pintype "unspecified"))
      (node (ref "USB1") (pin "2") (pinfunction "D-_2") (pintype "input"))
    )
    (net (code "47") (name "/USER_KEY") (class "Default")
      (node (ref "R41") (pin "1") (pinfunction "1_1") (pintype "unspecified"))
      (node (ref "U10") (pin "21") (pinfunction "P3.3/INT1_21") (pintype "unspecified"))
    )
    (net (code "48") (name "DC_IN") (class "Default")
      (node (ref "C1") (pin "2") (pinfunction "2_2") (pintype "unspecified"))
      (node (ref "C12") (pin "1") (pinfunction "1_1") (pintype "input"))
      (node (ref "C13") (pin "1") (pinfunction "1_1") (pintype "input"))
      (node (ref "C2") (pin "2") (pinfunction "2_2") (pintype "unspecified"))
      (node (ref "CN3") (pin "8") (pinfunction "8_8") (pintype "unspecified"))
      (node (ref "DC1") (pin "1") (pinfunction "1_1") (pintype "unspecified"))
      (node (ref "U1") (pin "2") (pinfunction "IN_2") (pintype "unspecified"))
      (node (ref "U3") (pin "13") (pinfunction "VM2_13") (pintype "unspecified"))
      (node (ref "U3") (pin "14") (pinfunction "VM3_14") (pintype "unspecified"))
      (node (ref "U3") (pin "24") (pinfunction "VM1_24") (pintype "unspecified"))
    )
    (net (code "49") (name "DIN_1") (class "Default")
      (node (ref "R31") (pin "2") (pinfunction "2_2") (pintype "unspecified"))
      (node (ref "U10") (pin "22") (pinfunction "P3.4/T0/T1CLKO/ECI_2_22") (pintype "bidirectional"))
      (node (ref "U7") (pin "4") (pinfunction "4_4") (pintype "unspecified"))
    )
    (net (code "50") (name "DIN_2") (class "Default")
      (node (ref "R34") (pin "2") (pinfunction "2_2") (pintype "unspecified"))
      (node (ref "U10") (pin "23") (pinfunction "P3.5/T1/T0CLKO/CCP0_2_23") (pintype "unspecified"))
      (node (ref "U8") (pin "4") (pinfunction "4_4") (pintype "unspecified"))
    )
    (net (code "51") (name "DIN_3") (class "Default")
      (node (ref "R37") (pin "2") (pinfunction "2_2") (pintype "unspecified"))
      (node (ref "U10") (pin "24") (pinfunction "P3.6/INT2/RXD_2/CCP1_2_24") (pintype "unspecified"))
      (node (ref "U9") (pin "4") (pinfunction "4_4") (pintype "unspecified"))
    )
    (net (code "52") (name "DIN_4") (class "Default")
      (node (ref "R38") (pin "2") (pinfunction "2_2") (pintype "unspecified"))
      (node (ref "U10") (pin "25") (pinfunction "P3.7/INT3/TXD_2/CCP2/CCP2_2_25") (pintype "unspecified"))
      (node (ref "U11") (pin "4") (pinfunction "4_4") (pintype "unspecified"))
    )
    (net (code "53") (name "GND") (class "Default")
      (node (ref "B1") (pin "2") (pinfunction "2_2") (pintype "input"))
      (node (ref "C1") (pin "1") (pinfunction "1_1") (pintype "unspecified"))
      (node (ref "C10") (pin "2") (pinfunction "2_2") (pintype "unspecified"))
      (node (ref "C11") (pin "1") (pinfunction "1_1") (pintype "unspecified"))
      (node (ref "C12") (pin "2") (pinfunction "2_2") (pintype "input"))
      (node (ref "C13") (pin "2") (pinfunction "2_2") (pintype "input"))
      (node (ref "C14") (pin "1") (pinfunction "1_1") (pintype "unspecified"))
      (node (ref "C15") (pin "2") (pinfunction "2_2") (pintype "input"))
      (node (ref "C16") (pin "2") (pinfunction "2_2") (pintype "unspecified"))
      (node (ref "C17") (pin "1") (pinfunction "1_1") (pintype "unspecified"))
      (node (ref "C18") (pin "2") (pinfunction "2_2") (pintype "unspecified"))
      (node (ref "C2") (pin "1") (pinfunction "1_1") (pintype "unspecified"))
      (node (ref "C20") (pin "1") (pinfunction "1_1") (pintype "unspecified"))
      (node (ref "C21") (pin "2") (pinfunction "2_2") (pintype "unspecified"))
      (node (ref "C22") (pin "2") (pinfunction "2_2") (pintype "unspecified"))
      (node (ref "C23") (pin "2") (pinfunction "2_2") (pintype "unspecified"))
      (node (ref "C24") (pin "2") (pinfunction "2_2") (pintype "unspecified"))
      (node (ref "C25") (pin "2") (pinfunction "2_2") (pintype "unspecified"))
      (node (ref "C3") (pin "1") (pinfunction "1_1") (pintype "unspecified"))
      (node (ref "C5") (pin "1") (pinfunction "1_1") (pintype "unspecified"))
      (node (ref "C53") (pin "2") (pinfunction "2_2") (pintype "unspecified"))
      (node (ref "C54") (pin "2") (pinfunction "2_2") (pintype "unspecified"))
      (node (ref "C7") (pin "2") (pinfunction "2_2") (pintype "unspecified"))
      (node (ref "C8") (pin "2") (pinfunction "2_2") (pintype "unspecified"))
      (node (ref "C9") (pin "1") (pinfunction "1_1") (pintype "unspecified"))
      (node (ref "CN1") (pin "6") (pinfunction "6_6") (pintype "unspecified"))
      (node (ref "CN3") (pin "6") (pinfunction "6_6") (pintype "unspecified"))
      (node (ref "D1") (pin "2") (pinfunction "A_2") (pintype "unspecified"))
      (node (ref "DC1") (pin "2") (pinfunction "2_2") (pintype "unspecified"))
      (node (ref "DC1") (pin "3") (pinfunction "3_3") (pintype "unspecified"))
      (node (ref "H2") (pin "9") (pinfunction "9_9") (pintype "unspecified"))
      (node (ref "KEY1") (pin "3") (pinfunction "3_3") (pintype "unspecified"))
      (node (ref "KEY1") (pin "4") (pinfunction "4_4") (pintype "unspecified"))
      (node (ref "LED4") (pin "2") (pinfunction "2_2") (pintype "unspecified"))
      (node (ref "R2") (pin "1") (pinfunction "1_1") (pintype "unspecified"))
      (node (ref "R3") (pin "2") (pinfunction "2_2") (pintype "unspecified"))
      (node (ref "U1") (pin "4") (pinfunction "GND_4") (pintype "unspecified"))
      (node (ref "U1") (pin "9") (pinfunction "9_9") (pintype "unspecified"))
      (node (ref "U10") (pin "16") (pinfunction "GND_16") (pintype "unspecified"))
      (node (ref "U11") (pin "3") (pinfunction "3_3") (pintype "unspecified"))
      (node (ref "U12") (pin "1") (pinfunction "A0_1") (pintype "unspecified"))
      (node (ref "U12") (pin "2") (pinfunction "A1_2") (pintype "unspecified"))
      (node (ref "U12") (pin "3") (pinfunction "A2_3") (pintype "unspecified"))
      (node (ref "U12") (pin "4") (pinfunction "GND_4") (pintype "unspecified"))
      (node (ref "U12") (pin "7") (pinfunction "WP_7") (pintype "unspecified"))
      (node (ref "U13") (pin "2") (pinfunction "GND_2") (pintype "unspecified"))
      (node (ref "U18") (pin "1") (pinfunction "GND_1") (pintype "unspecified"))
      (node (ref "U2") (pin "1") (pinfunction "GND_1") (pintype "unspecified"))
      (node (ref "U3") (pin "10") (pinfunction "PGND2_10") (pintype "unspecified"))
      (node (ref "U3") (pin "18") (pinfunction "GND_18") (pintype "unspecified"))
      (node (ref "U3") (pin "3") (pinfunction "PGND1_3") (pintype "unspecified"))
      (node (ref "U3") (pin "4") (pinfunction "PGND1_4") (pintype "unspecified"))
      (node (ref "U3") (pin "9") (pinfunction "PGND2_9") (pintype "unspecified"))
      (node (ref "U4") (pin "4") (pinfunction "VSS_4") (pintype "unspecified"))
      (node (ref "U5") (pin "1") (pinfunction "OE_1") (pintype "unspecified"))
      (node (ref "U5") (pin "10") (pinfunction "GND_10") (pintype "unspecified"))
      (node (ref "U7") (pin "3") (pinfunction "3_3") (pintype "unspecified"))
      (node (ref "U8") (pin "3") (pinfunction "3_3") (pintype "unspecified"))
      (node (ref "U9") (pin "3") (pinfunction "3_3") (pintype "unspecified"))
      (node (ref "USB1") (pin "4") (pinfunction "GND_4") (pintype "input"))
      (node (ref "USB1") (pin "5") (pinfunction "SH1_5") (pintype "unspecified"))
      (node (ref "USB1") (pin "6") (pinfunction "SH2_6") (pintype "unspecified"))
    )
    (net (code "54") (name "LE_COM") (class "Default")
      (node (ref "U10") (pin "10") (pinfunction "P1.5/ADC5/SCLK_10") (pintype "unspecified"))
    )
    (net (code "55") (name "LE_SEG") (class "Default")
      (node (ref "C20") (pin "2") (pinfunction "2_2") (pintype "unspecified"))
      (node (ref "U10") (pin "9") (pinfunction "P1.4/ADC4/MISO_9") (pintype "unspecified"))
      (node (ref "U5") (pin "11") (pinfunction "LE_11") (pintype "unspecified"))
    )
    (net (code "56") (name "M1_IN1") (class "Default")
      (node (ref "R8") (pin "2") (pinfunction "2_2") (pintype "unspecified"))
      (node (ref "U3") (pin "21") (pinfunction "AIN1_21") (pintype "unspecified"))
    )
    (net (code "57") (name "M1_IN2") (class "Default")
      (node (ref "R9") (pin "2") (pinfunction "2_2") (pintype "unspecified"))
      (node (ref "U3") (pin "22") (pinfunction "AIN2_22") (pintype "unspecified"))
    )
    (net (code "58") (name "M1_PWM") (class "Default")
      (node (ref "R6") (pin "2") (pinfunction "2_2") (pintype "unspecified"))
      (node (ref "U3") (pin "23") (pinfunction "PWMA_23") (pintype "unspecified"))
    )
    (net (code "59") (name "M2_IN1") (class "Default")
      (node (ref "R10") (pin "2") (pinfunction "2_2") (pintype "unspecified"))
      (node (ref "U3") (pin "17") (pinfunction "BIN1_17") (pintype "unspecified"))
    )
    (net (code "60") (name "M2_IN2") (class "Default")
      (node (ref "R11") (pin "2") (pinfunction "2_2") (pintype "unspecified"))
      (node (ref "U3") (pin "16") (pinfunction "BIN2_16") (pintype "unspecified"))
    )
    (net (code "61") (name "M2_PWM") (class "Default")
      (node (ref "R12") (pin "2") (pinfunction "2_2") (pintype "unspecified"))
      (node (ref "U3") (pin "15") (pinfunction "PWMB_15") (pintype "unspecified"))
    )
    (net (code "62") (name "Net-(B1-Pad1)") (class "Default")
      (node (ref "B1") (pin "1") (pinfunction "1_1") (pintype "input"))
      (node (ref "D3") (pin "2") (pinfunction "2_2") (pintype "unspecified"))
    )
    (net (code "63") (name "Net-(C4-Pad1)") (class "Default")
      (node (ref "C4") (pin "1") (pinfunction "1_1") (pintype "unspecified"))
      (node (ref "R3") (pin "1") (pinfunction "1_1") (pintype "unspecified"))
    )
    (net (code "64") (name "Net-(C6-Pad2)") (class "Default")
      (node (ref "C6") (pin "2") (pinfunction "2_2") (pintype "unspecified"))
      (node (ref "R4") (pin "2") (pinfunction "2_2") (pintype "unspecified"))
    )
    (net (code "65") (name "Net-(C25-Pad1)") (class "Default")
      (node (ref "C25") (pin "1") (pinfunction "1_1") (pintype "unspecified"))
      (node (ref "KEY1") (pin "1") (pinfunction "1_1") (pintype "unspecified"))
      (node (ref "KEY1") (pin "2") (pinfunction "2_2") (pintype "unspecified"))
      (node (ref "R41") (pin "2") (pinfunction "2_2") (pintype "unspecified"))
      (node (ref "R42") (pin "1") (pinfunction "1_1") (pintype "unspecified"))
    )
    (net (code "66") (name "Net-(CN1-Pad1)") (class "Default")
      (node (ref "CN1") (pin "1") (pinfunction "1_1") (pintype "unspecified"))
      (node (ref "R22") (pin "1") (pinfunction "1_1") (pintype "unspecified"))
      (node (ref "R25") (pin "2") (pinfunction "2_2") (pintype "unspecified"))
    )
    (net (code "67") (name "Net-(CN1-Pad2)") (class "Default")
      (node (ref "CN1") (pin "2") (pinfunction "2_2") (pintype "unspecified"))
      (node (ref "R21") (pin "1") (pinfunction "1_1") (pintype "unspecified"))
      (node (ref "R23") (pin "2") (pinfunction "2_2") (pintype "unspecified"))
    )
    (net (code "68") (name "Net-(CN1-Pad3)") (class "Default")
      (node (ref "CN1") (pin "3") (pinfunction "3_3") (pintype "unspecified"))
      (node (ref "R26") (pin "1") (pinfunction "1_1") (pintype "unspecified"))
      (node (ref "R28") (pin "2") (pinfunction "2_2") (pintype "unspecified"))
    )
    (net (code "69") (name "Net-(CN1-Pad4)") (class "Default")
      (node (ref "CN1") (pin "4") (pinfunction "4_4") (pintype "unspecified"))
      (node (ref "R27") (pin "1") (pinfunction "1_1") (pintype "unspecified"))
      (node (ref "R29") (pin "2") (pinfunction "2_2") (pintype "unspecified"))
    )
    (net (code "70") (name "Net-(D1-K)") (class "Default")
      (node (ref "D1") (pin "1") (pinfunction "K_1") (pintype "unspecified"))
      (node (ref "L1") (pin "2") (pinfunction "2_2") (pintype "unspecified"))
      (node (ref "R4") (pin "1") (pinfunction "1_1") (pintype "unspecified"))
      (node (ref "U1") (pin "3") (pinfunction "SW_3") (pintype "unspecified"))
    )
    (net (code "71") (name "Net-(LED4-Pad1)") (class "Default")
      (node (ref "LED4") (pin "1") (pinfunction "1_1") (pintype "unspecified"))
      (node (ref "R24") (pin "1") (pinfunction "1_1") (pintype "unspecified"))
    )
    (net (code "72") (name "Net-(M1-Pad1)") (class "Default")
      (node (ref "M1") (pin "1") (pinfunction "1_1") (pintype "unspecified"))
      (node (ref "U3") (pin "1") (pinfunction "AO1_1") (pintype "unspecified"))
      (node (ref "U3") (pin "2") (pinfunction "AO1_2") (pintype "unspecified"))
    )
    (net (code "73") (name "Net-(M1-Pad2)") (class "Default")
      (node (ref "M1") (pin "2") (pinfunction "2_2") (pintype "unspecified"))
      (node (ref "U3") (pin "5") (pinfunction "AO2_5") (pintype "unspecified"))
      (node (ref "U3") (pin "6") (pinfunction "AO2_6") (pintype "unspecified"))
    )
    (net (code "74") (name "Net-(M2-Pad1)") (class "Default")
      (node (ref "M2") (pin "1") (pinfunction "1_1") (pintype "unspecified"))
      (node (ref "U3") (pin "11") (pinfunction "BO1_11") (pintype "unspecified"))
      (node (ref "U3") (pin "12") (pinfunction "BO1_12") (pintype "unspecified"))
    )
    (net (code "75") (name "Net-(M2-Pad2)") (class "Default")
      (node (ref "M2") (pin "2") (pinfunction "2_2") (pintype "unspecified"))
      (node (ref "U3") (pin "7") (pinfunction "BO2_7") (pintype "unspecified"))
      (node (ref "U3") (pin "8") (pinfunction "BO2_8") (pintype "unspecified"))
    )
    (net (code "76") (name "Net-(R30-Pad2)") (class "Default")
      (node (ref "R30") (pin "2") (pinfunction "2_2") (pintype "unspecified"))
      (node (ref "U7") (pin "1") (pinfunction "1_1") (pintype "unspecified"))
    )
    (net (code "77") (name "Net-(R35-Pad2)") (class "Default")
      (node (ref "R35") (pin "2") (pinfunction "2_2") (pintype "unspecified"))
      (node (ref "U8") (pin "1") (pinfunction "1_1") (pintype "unspecified"))
    )
    (net (code "78") (name "Net-(R36-Pad2)") (class "Default")
      (node (ref "R36") (pin "2") (pinfunction "2_2") (pintype "unspecified"))
      (node (ref "U9") (pin "1") (pinfunction "1_1") (pintype "unspecified"))
    )
    (net (code "79") (name "Net-(R39-Pad2)") (class "Default")
      (node (ref "R39") (pin "2") (pinfunction "2_2") (pintype "unspecified"))
      (node (ref "U11") (pin "1") (pinfunction "1_1") (pintype "unspecified"))
    )
    (net (code "80") (name "Net-(U1-BS)") (class "Default")
      (node (ref "C6") (pin "1") (pinfunction "1_1") (pintype "unspecified"))
      (node (ref "U1") (pin "1") (pinfunction "BS_1") (pintype "unspecified"))
    )
    (net (code "81") (name "Net-(U1-COMP)") (class "Default")
      (node (ref "C4") (pin "2") (pinfunction "2_2") (pintype "unspecified"))
      (node (ref "C5") (pin "2") (pinfunction "2_2") (pintype "unspecified"))
      (node (ref "U1") (pin "6") (pinfunction "COMP_6") (pintype "unspecified"))
    )
    (net (code "82") (name "Net-(U1-FB)") (class "Default")
      (node (ref "R1") (pin "2") (pinfunction "2_2") (pintype "unspecified"))
      (node (ref "R2") (pin "2") (pinfunction "2_2") (pintype "unspecified"))
      (node (ref "U1") (pin "5") (pinfunction "FB_5") (pintype "unspecified"))
    )
    (net (code "83") (name "Net-(U1-SS)") (class "Default")
      (node (ref "C3") (pin "2") (pinfunction "2_2") (pintype "unspecified"))
      (node (ref "U1") (pin "8") (pinfunction "SS_8") (pintype "unspecified"))
    )
    (net (code "84") (name "Net-(U2-RXD)") (class "Default")
      (node (ref "R5") (pin "2") (pinfunction "2_2") (pintype "unspecified"))
      (node (ref "U2") (pin "3") (pinfunction "RXD_3") (pintype "unspecified"))
    )
    (net (code "85") (name "Net-(U2-TXD)") (class "Default")
      (node (ref "R7") (pin "2") (pinfunction "2_2") (pintype "unspecified"))
      (node (ref "U2") (pin "2") (pinfunction "TXD_2") (pintype "unspecified"))
    )
    (net (code "86") (name "Net-(U4-OSCI)") (class "Default")
      (node (ref "U4") (pin "1") (pinfunction "OSCI_1") (pintype "unspecified"))
      (node (ref "X2") (pin "2") (pinfunction "OSC2_2") (pintype "unspecified"))
    )
    (net (code "87") (name "Net-(U4-OSCO)") (class "Default")
      (node (ref "C14") (pin "2") (pinfunction "2_2") (pintype "unspecified"))
      (node (ref "U4") (pin "2") (pinfunction "OSCO_2") (pintype "unspecified"))
      (node (ref "X2") (pin "1") (pinfunction "OSC1_1") (pintype "unspecified"))
    )
    (net (code "88") (name "Net-(U4-VDD)") (class "Default")
      (node (ref "C15") (pin "1") (pinfunction "1_1") (pintype "input"))
      (node (ref "D2") (pin "1") (pinfunction "1_1") (pintype "unspecified"))
      (node (ref "D3") (pin "1") (pinfunction "1_1") (pintype "unspecified"))
      (node (ref "U4") (pin "8") (pinfunction "VDD_8") (pintype "unspecified"))
    )
    (net (code "89") (name "Net-(U5-Q0)") (class "Default")
      (node (ref "R13") (pin "1") (pinfunction "1_1") (pintype "unspecified"))
      (node (ref "U5") (pin "19") (pinfunction "Q0_19") (pintype "unspecified"))
    )
    (net (code "90") (name "Net-(U5-Q1)") (class "Default")
      (node (ref "R14") (pin "1") (pinfunction "1_1") (pintype "unspecified"))
      (node (ref "U5") (pin "18") (pinfunction "Q1_18") (pintype "unspecified"))
    )
    (net (code "91") (name "Net-(U5-Q2)") (class "Default")
      (node (ref "R15") (pin "1") (pinfunction "1_1") (pintype "unspecified"))
      (node (ref "U5") (pin "17") (pinfunction "Q2_17") (pintype "unspecified"))
    )
    (net (code "92") (name "Net-(U5-Q3)") (class "Default")
      (node (ref "R16") (pin "1") (pinfunction "1_1") (pintype "unspecified"))
      (node (ref "U5") (pin "16") (pinfunction "Q3_16") (pintype "unspecified"))
    )
    (net (code "93") (name "Net-(U5-Q4)") (class "Default")
      (node (ref "R17") (pin "1") (pinfunction "1_1") (pintype "unspecified"))
      (node (ref "U5") (pin "15") (pinfunction "Q4_15") (pintype "unspecified"))
    )
    (net (code "94") (name "Net-(U5-Q5)") (class "Default")
      (node (ref "R18") (pin "1") (pinfunction "1_1") (pintype "unspecified"))
      (node (ref "U5") (pin "14") (pinfunction "Q5_14") (pintype "unspecified"))
    )
    (net (code "95") (name "Net-(U5-Q6)") (class "Default")
      (node (ref "R19") (pin "1") (pinfunction "1_1") (pintype "unspecified"))
      (node (ref "U5") (pin "13") (pinfunction "Q6_13") (pintype "unspecified"))
    )
    (net (code "96") (name "Net-(U5-Q7)") (class "Default")
      (node (ref "R20") (pin "1") (pinfunction "1_1") (pintype "unspecified"))
      (node (ref "U5") (pin "12") (pinfunction "Q7_12") (pintype "unspecified"))
    )
    (net (code "97") (name "Net-(U10-P1.0{slash}ADC0{slash}CCP1{slash}RXD2)") (class "Default")
      (node (ref "C21") (pin "1") (pinfunction "1_1") (pintype "unspecified"))
      (node (ref "R22") (pin "2") (pinfunction "2_2") (pintype "unspecified"))
      (node (ref "U10") (pin "4") (pinfunction "P1.0/ADC0/CCP1/RXD2_4") (pintype "unspecified"))
    )
    (net (code "98") (name "Net-(U10-P1.1{slash}ADC1{slash}CCP0{slash}TXD2)") (class "Default")
      (node (ref "C22") (pin "1") (pinfunction "1_1") (pintype "unspecified"))
      (node (ref "R21") (pin "2") (pinfunction "2_2") (pintype "unspecified"))
      (node (ref "U10") (pin "5") (pinfunction "P1.1/ADC1/CCP0/TXD2_5") (pintype "unspecified"))
    )
    (net (code "99") (name "Net-(U10-P1.2{slash}ADC2{slash}SS{slash}ECI)") (class "Default")
      (node (ref "C23") (pin "1") (pinfunction "1_1") (pintype "unspecified"))
      (node (ref "R26") (pin "2") (pinfunction "2_2") (pintype "unspecified"))
      (node (ref "U10") (pin "7") (pinfunction "P1.2/ADC2/SS/ECI_7") (pintype "unspecified"))
    )
    (net (code "100") (name "Net-(U10-P1.3{slash}ADC3{slash}MOSI)") (class "Default")
      (node (ref "C24") (pin "1") (pinfunction "1_1") (pintype "unspecified"))
      (node (ref "R27") (pin "2") (pinfunction "2_2") (pintype "unspecified"))
      (node (ref "U10") (pin "8") (pinfunction "P1.3/ADC3/MOSI_8") (pintype "unspecified"))
    )
    (net (code "101") (name "Net-(U10-P2.2{slash}MISO_2)") (class "Default")
      (node (ref "R6") (pin "1") (pinfunction "1_1") (pintype "unspecified"))
      (node (ref "U10") (pin "32") (pinfunction "P2.2/MISO_2_32") (pintype "bidirectional"))
    )
    (net (code "102") (name "Net-(U10-P2.3{slash}MOSI_2)") (class "Default")
      (node (ref "R8") (pin "1") (pinfunction "1_1") (pintype "unspecified"))
      (node (ref "U10") (pin "33") (pinfunction "P2.3/MOSI_2_33") (pintype "bidirectional"))
    )
    (net (code "103") (name "Net-(U10-P2.4{slash}ECI_3{slash}SS_2)") (class "Default")
      (node (ref "R9") (pin "1") (pinfunction "1_1") (pintype "unspecified"))
      (node (ref "U10") (pin "34") (pinfunction "P2.4/ECI_3/SS_2_34") (pintype "bidirectional"))
    )
    (net (code "104") (name "Net-(U10-P2.5{slash}CCP0_3)") (class "Default")
      (node (ref "R10") (pin "1") (pinfunction "1_1") (pintype "unspecified"))
      (node (ref "U10") (pin "35") (pinfunction "P2.5/CCP0_3_35") (pintype "bidirectional"))
    )
    (net (code "105") (name "Net-(U10-P2.6{slash}CCP1_3)") (class "Default")
      (node (ref "R11") (pin "1") (pinfunction "1_1") (pintype "unspecified"))
      (node (ref "U10") (pin "36") (pinfunction "P2.6/CCP1_3_36") (pintype "bidirectional"))
    )
    (net (code "106") (name "Net-(U10-P2.7{slash}CCP2_3)") (class "Default")
      (node (ref "R12") (pin "1") (pinfunction "1_1") (pintype "unspecified"))
      (node (ref "U10") (pin "37") (pinfunction "P2.7/CCP2_3_37") (pintype "bidirectional"))
    )
    (net (code "107") (name "Net-(USB1-VCC)") (class "Default")
      (node (ref "F1") (pin "1") (pinfunction "1_1") (pintype "unspecified"))
      (node (ref "USB1") (pin "1") (pinfunction "VCC_1") (pintype "input"))
    )
    (net (code "108") (name "VUSB") (class "Default")
      (node (ref "C54") (pin "1") (pinfunction "1_1") (pintype "unspecified"))
      (node (ref "F1") (pin "2") (pinfunction "2_2") (pintype "unspecified"))
      (node (ref "U18") (pin "2") (pinfunction "VIN_2") (pintype "unspecified"))
    )
    (net (code "109") (name "unconnected-(C19-Pad1)") (class "Default")
      (node (ref "C19") (pin "1") (pinfunction "1_1") (pintype "unspecified"))
    )
    (net (code "110") (name "unconnected-(C19-Pad2)") (class "Default")
      (node (ref "C19") (pin "2") (pinfunction "2_2") (pintype "unspecified"))
    )
    (net (code "111") (name "unconnected-(C26-Pad1)") (class "Default")
      (node (ref "C26") (pin "1") (pinfunction "1_1") (pintype "unspecified"))
    )
    (net (code "112") (name "unconnected-(C26-Pad2)") (class "Default")
      (node (ref "C26") (pin "2") (pinfunction "2_2") (pintype "unspecified"))
    )
    (net (code "113") (name "unconnected-(CN3-Pad7)") (class "Default")
      (node (ref "CN3") (pin "7") (pinfunction "7_7") (pintype "unspecified+no_connect"))
    )
    (net (code "114") (name "unconnected-(U1-EN-Pad7)") (class "Default")
      (node (ref "U1") (pin "7") (pinfunction "EN_7") (pintype "unspecified+no_connect"))
    )
    (net (code "115") (name "unconnected-(U2-CTS#-Pad9)") (class "Default")
      (node (ref "U2") (pin "9") (pinfunction "CTS#_9") (pintype "unspecified+no_connect"))
    )
    (net (code "116") (name "unconnected-(U2-DCD#-Pad12)") (class "Default")
      (node (ref "U2") (pin "12") (pinfunction "DCD#_12") (pintype "unspecified+no_connect"))
    )
    (net (code "117") (name "unconnected-(U2-DSR#-Pad10)") (class "Default")
      (node (ref "U2") (pin "10") (pinfunction "DSR#_10") (pintype "unspecified+no_connect"))
    )
    (net (code "118") (name "unconnected-(U2-DTR#-Pad13)") (class "Default")
      (node (ref "U2") (pin "13") (pinfunction "DTR#_13") (pintype "unspecified+no_connect"))
    )
    (net (code "119") (name "unconnected-(U2-NC.-Pad7)") (class "Default")
      (node (ref "U2") (pin "7") (pinfunction "NC._7") (pintype "unspecified+no_connect"))
    )
    (net (code "120") (name "unconnected-(U2-OUT#-Pad8)") (class "Default")
      (node (ref "U2") (pin "8") (pinfunction "OUT#_8") (pintype "unspecified+no_connect"))
    )
    (net (code "121") (name "unconnected-(U2-R232-Pad15)") (class "Default")
      (node (ref "U2") (pin "15") (pinfunction "R232_15") (pintype "unspecified+no_connect"))
    )
    (net (code "122") (name "unconnected-(U2-RI#-Pad11)") (class "Default")
      (node (ref "U2") (pin "11") (pinfunction "RI#_11") (pintype "unspecified+no_connect"))
    )
    (net (code "123") (name "unconnected-(U2-RTS#-Pad14)") (class "Default")
      (node (ref "U2") (pin "14") (pinfunction "RTS#_14") (pintype "unspecified+no_connect"))
    )
    (net (code "124") (name "unconnected-(U4-CLKOUT-Pad7)") (class "Default")
      (node (ref "U4") (pin "7") (pinfunction "CLKOUT_7") (pintype "unspecified+no_connect"))
    )
    (net (code "125") (name "unconnected-(U4-INT#-Pad3)") (class "Default")
      (node (ref "U4") (pin "3") (pinfunction "INT#_3") (pintype "unspecified+no_connect"))
    )
    (net (code "126") (name "unconnected-(U6-D0-Pad2)") (class "Default")
      (node (ref "U6") (pin "2") (pinfunction "D0_2") (pintype "unspecified"))
    )
    (net (code "127") (name "unconnected-(U6-D1-Pad3)") (class "Default")
      (node (ref "U6") (pin "3") (pinfunction "D1_3") (pintype "unspecified"))
    )
    (net (code "128") (name "unconnected-(U6-D2-Pad4)") (class "Default")
      (node (ref "U6") (pin "4") (pinfunction "D2_4") (pintype "unspecified"))
    )
    (net (code "129") (name "unconnected-(U6-D3-Pad5)") (class "Default")
      (node (ref "U6") (pin "5") (pinfunction "D3_5") (pintype "unspecified"))
    )
    (net (code "130") (name "unconnected-(U6-D4-Pad6)") (class "Default")
      (node (ref "U6") (pin "6") (pinfunction "D4_6") (pintype "unspecified"))
    )
    (net (code "131") (name "unconnected-(U6-D5-Pad7)") (class "Default")
      (node (ref "U6") (pin "7") (pinfunction "D5_7") (pintype "unspecified"))
    )
    (net (code "132") (name "unconnected-(U6-D6-Pad8)") (class "Default")
      (node (ref "U6") (pin "8") (pinfunction "D6_8") (pintype "unspecified"))
    )
    (net (code "133") (name "unconnected-(U6-D7-Pad9)") (class "Default")
      (node (ref "U6") (pin "9") (pinfunction "D7_9") (pintype "unspecified"))
    )
    (net (code "134") (name "unconnected-(U6-GND-Pad10)") (class "Default")
      (node (ref "U6") (pin "10") (pinfunction "GND_10") (pintype "unspecified"))
    )
    (net (code "135") (name "unconnected-(U6-LE-Pad11)") (class "Default")
      (node (ref "U6") (pin "11") (pinfunction "LE_11") (pintype "unspecified"))
    )
    (net (code "136") (name "unconnected-(U6-OE-Pad1)") (class "Default")
      (node (ref "U6") (pin "1") (pinfunction "OE_1") (pintype "unspecified"))
    )
    (net (code "137") (name "unconnected-(U6-Q0-Pad19)") (class "Default")
      (node (ref "U6") (pin "19") (pinfunction "Q0_19") (pintype "unspecified"))
    )
    (net (code "138") (name "unconnected-(U6-Q1-Pad18)") (class "Default")
      (node (ref "U6") (pin "18") (pinfunction "Q1_18") (pintype "unspecified"))
    )
    (net (code "139") (name "unconnected-(U6-Q2-Pad17)") (class "Default")
      (node (ref "U6") (pin "17") (pinfunction "Q2_17") (pintype "unspecified"))
    )
    (net (code "140") (name "unconnected-(U6-Q3-Pad16)") (class "Default")
      (node (ref "U6") (pin "16") (pinfunction "Q3_16") (pintype "unspecified"))
    )
    (net (code "141") (name "unconnected-(U6-Q4-Pad15)") (class "Default")
      (node (ref "U6") (pin "15") (pinfunction "Q4_15") (pintype "unspecified"))
    )
    (net (code "142") (name "unconnected-(U6-Q5-Pad14)") (class "Default")
      (node (ref "U6") (pin "14") (pinfunction "Q5_14") (pintype "unspecified"))
    )
    (net (code "143") (name "unconnected-(U6-Q6-Pad13)") (class "Default")
      (node (ref "U6") (pin "13") (pinfunction "Q6_13") (pintype "unspecified"))
    )
    (net (code "144") (name "unconnected-(U6-Q7-Pad12)") (class "Default")
      (node (ref "U6") (pin "12") (pinfunction "Q7_12") (pintype "unspecified"))
    )
    (net (code "145") (name "unconnected-(U6-VCC-Pad20)") (class "Default")
      (node (ref "U6") (pin "20") (pinfunction "VCC_20") (pintype "unspecified"))
    )
    (net (code "146") (name "unconnected-(U10-P1.6{slash}ADC6{slash}RXD_3{slash}XTAL2-Pad11)") (class "Default")
      (node (ref "U10") (pin "11") (pinfunction "P1.6/ADC6/RXD_3/XTAL2_11") (pintype "bidirectional+no_connect"))
    )
    (net (code "147") (name "unconnected-(U10-P1.7{slash}ADC7{slash}TXD_3{slash}XTAL1-Pad12)") (class "Default")
      (node (ref "U10") (pin "12") (pinfunction "P1.7/ADC7/TXD_3/XTAL1_12") (pintype "bidirectional+no_connect"))
    )
    (net (code "148") (name "unconnected-(U10-P5.4{slash}RST{slash}MCLK0{slash}SS_3-Pad13)") (class "Default")
      (node (ref "U10") (pin "13") (pinfunction "P5.4/RST/MCLK0/SS_3_13") (pintype "unspecified+no_connect"))
    )
  )
)
